# ProProject_caotai_ctrl_v2.net
KiCad netlist of a schematic drawn in EasyEDA Pro
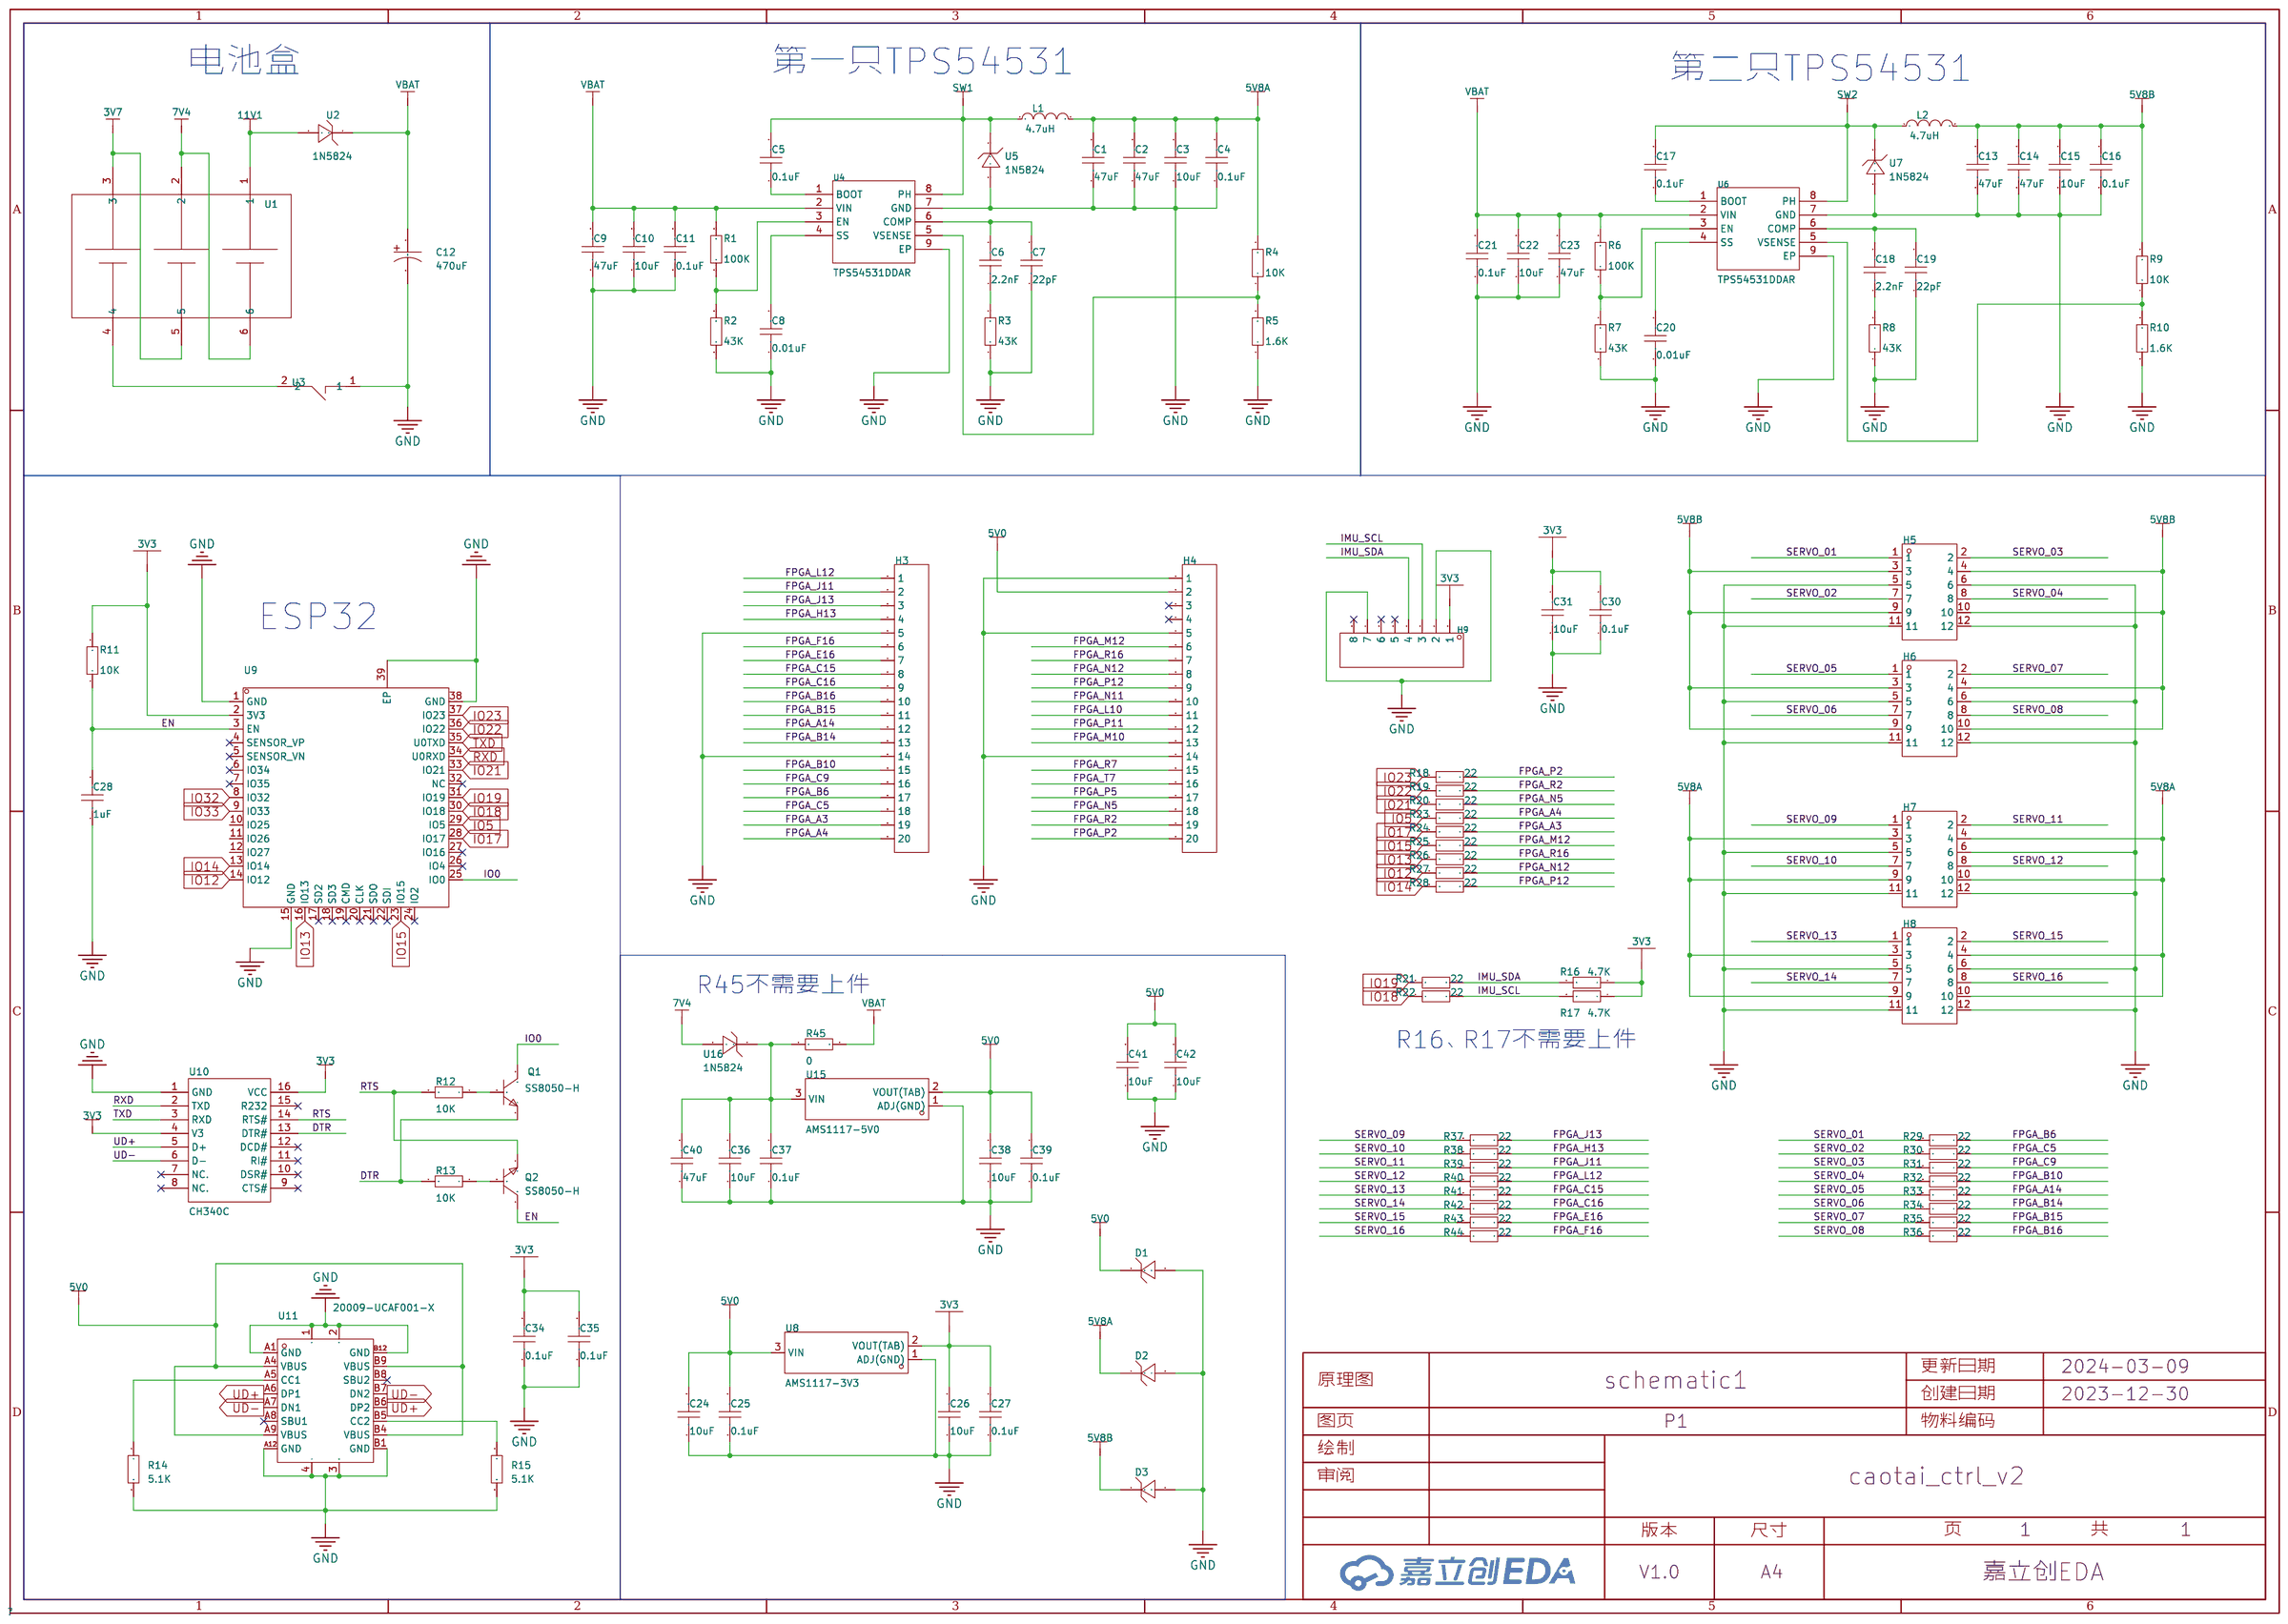
[diagram p0: schematic sheet]

(export (version "E")
  (design (tool "Eeschema 10.0.6"))
  (components
    (comp (ref "C1")
      (value "47uF")
      (footprint "easyedapro:C0603")
      (libsource (lib "easyedapro") (part "CapAcitance"))
    )
    (comp (ref "C2")
      (value "47uF")
      (footprint "easyedapro:C0603")
      (libsource (lib "easyedapro") (part "CapAcitance"))
    )
    (comp (ref "C3")
      (value "10uF")
      (footprint "easyedapro:C0603")
      (libsource (lib "easyedapro") (part "CapAcitance"))
    )
    (comp (ref "C4")
      (value "0.1uF")
      (footprint "easyedapro:C0603")
      (libsource (lib "easyedapro") (part "CapAcitance"))
    )
    (comp (ref "C5")
      (value "0.1uF")
      (footprint "easyedapro:C0603")
      (libsource (lib "easyedapro") (part "CapAcitance"))
    )
    (comp (ref "C6")
      (value "2.2nF")
      (footprint "easyedapro:C0603")
      (libsource (lib "easyedapro") (part "CapAcitance"))
    )
    (comp (ref "C7")
      (value "22pF")
      (footprint "easyedapro:C0603")
      (libsource (lib "easyedapro") (part "CapAcitance"))
    )
    (comp (ref "C8")
      (value "0.01uF")
      (footprint "easyedapro:C0603")
      (libsource (lib "easyedapro") (part "CapAcitance"))
    )
    (comp (ref "C9")
      (value "47uF")
      (footprint "easyedapro:C0603")
      (libsource (lib "easyedapro") (part "CapAcitance"))
    )
    (comp (ref "C10")
      (value "10uF")
      (footprint "easyedapro:C0603")
      (libsource (lib "easyedapro") (part "CapAcitance"))
    )
    (comp (ref "C11")
      (value "0.1uF")
      (footprint "easyedapro:C0603")
      (libsource (lib "easyedapro") (part "CapAcitance"))
    )
    (comp (ref "C12")
      (value "470uF")
      (footprint "easyedapro:CAP-TH_BD10.0-P5.00-D1.0-FD")
      (description "容值:470uF;精度:±20%;额定电压:25V;")
      (fields
        (field (name "Manufacturer Part") "NXB25VB470M10*16_5.0TP")
        (field (name "Manufacturer") "SAMYOUNG(韩国三莹)")
      )
      (libsource (lib "easyedapro") (part "NXB25VB470M10*16_5.0TP"))
    )
    (comp (ref "C13")
      (value "47uF")
      (footprint "easyedapro:C0603")
      (libsource (lib "easyedapro") (part "CapAcitance"))
    )
    (comp (ref "C14")
      (value "47uF")
      (footprint "easyedapro:C0603")
      (libsource (lib "easyedapro") (part "CapAcitance"))
    )
    (comp (ref "C15")
      (value "10uF")
      (footprint "easyedapro:C0603")
      (libsource (lib "easyedapro") (part "CapAcitance"))
    )
    (comp (ref "C16")
      (value "0.1uF")
      (footprint "easyedapro:C0603")
      (libsource (lib "easyedapro") (part "CapAcitance"))
    )
    (comp (ref "C17")
      (value "0.1uF")
      (footprint "easyedapro:C0603")
      (libsource (lib "easyedapro") (part "CapAcitance"))
    )
    (comp (ref "C18")
      (value "2.2nF")
      (footprint "easyedapro:C0603")
      (libsource (lib "easyedapro") (part "CapAcitance"))
    )
    (comp (ref "C19")
      (value "22pF")
      (footprint "easyedapro:C0603")
      (libsource (lib "easyedapro") (part "CapAcitance"))
    )
    (comp (ref "C20")
      (value "0.01uF")
      (footprint "easyedapro:C0603")
      (libsource (lib "easyedapro") (part "CapAcitance"))
    )
    (comp (ref "C21")
      (value "0.1uF")
      (footprint "easyedapro:C0603")
      (libsource (lib "easyedapro") (part "CapAcitance"))
    )
    (comp (ref "C22")
      (value "10uF")
      (footprint "easyedapro:C0603")
      (libsource (lib "easyedapro") (part "CapAcitance"))
    )
    (comp (ref "C23")
      (value "47uF")
      (footprint "easyedapro:C0603")
      (libsource (lib "easyedapro") (part "CapAcitance"))
    )
    (comp (ref "C24")
      (value "10uF")
      (footprint "easyedapro:C0603")
      (libsource (lib "easyedapro") (part "CapAcitance"))
    )
    (comp (ref "C25")
      (value "0.1uF")
      (footprint "easyedapro:C0603")
      (libsource (lib "easyedapro") (part "CapAcitance"))
    )
    (comp (ref "C26")
      (value "10uF")
      (footprint "easyedapro:C0603")
      (libsource (lib "easyedapro") (part "CapAcitance"))
    )
    (comp (ref "C27")
      (value "0.1uF")
      (footprint "easyedapro:C0603")
      (libsource (lib "easyedapro") (part "CapAcitance"))
    )
    (comp (ref "C28")
      (value "1uF")
      (footprint "easyedapro:C0603")
      (libsource (lib "easyedapro") (part "CapAcitance"))
    )
    (comp (ref "C30")
      (value "0.1uF")
      (footprint "easyedapro:C0603")
      (libsource (lib "easyedapro") (part "CapAcitance"))
    )
    (comp (ref "C31")
      (value "10uF")
      (footprint "easyedapro:C0603")
      (libsource (lib "easyedapro") (part "CapAcitance"))
    )
    (comp (ref "C34")
      (value "0.1uF")
      (footprint "easyedapro:C0603")
      (libsource (lib "easyedapro") (part "CapAcitance"))
    )
    (comp (ref "C35")
      (value "0.1uF")
      (footprint "easyedapro:C0603")
      (libsource (lib "easyedapro") (part "CapAcitance"))
    )
    (comp (ref "C36")
      (value "10uF")
      (footprint "easyedapro:C0603")
      (libsource (lib "easyedapro") (part "CapAcitance"))
    )
    (comp (ref "C37")
      (value "0.1uF")
      (footprint "easyedapro:C0603")
      (libsource (lib "easyedapro") (part "CapAcitance"))
    )
    (comp (ref "C38")
      (value "10uF")
      (footprint "easyedapro:C0603")
      (libsource (lib "easyedapro") (part "CapAcitance"))
    )
    (comp (ref "C39")
      (value "0.1uF")
      (footprint "easyedapro:C0603")
      (libsource (lib "easyedapro") (part "CapAcitance"))
    )
    (comp (ref "C40")
      (value "47uF")
      (footprint "easyedapro:C0603")
      (libsource (lib "easyedapro") (part "CapAcitance"))
    )
    (comp (ref "C41")
      (value "10uF")
      (footprint "easyedapro:C0603")
      (libsource (lib "easyedapro") (part "CapAcitance"))
    )
    (comp (ref "C42")
      (value "10uF")
      (footprint "easyedapro:C0603")
      (libsource (lib "easyedapro") (part "CapAcitance"))
    )
    (comp (ref "D1")
      (value "SMBJ24CD-M3/I")
      (footprint "easyedapro:SMB_L4.6-W3.6-LS5.3-RD")
      (fields (field (name "Manufacturer") "VISHAY(威世)"))
      (libsource (lib "easyedapro") (part "SMBJ24CD-M3/I"))
    )
    (comp (ref "D2")
      (value "SMBJ24CD-M3/I")
      (footprint "easyedapro:SMB_L4.6-W3.6-LS5.3-RD")
      (fields (field (name "Manufacturer") "VISHAY(威世)"))
      (libsource (lib "easyedapro") (part "SMBJ24CD-M3/I"))
    )
    (comp (ref "D3")
      (value "SMBJ24CD-M3/I")
      (footprint "easyedapro:SMB_L4.6-W3.6-LS5.3-RD")
      (fields (field (name "Manufacturer") "VISHAY(威世)"))
      (libsource (lib "easyedapro") (part "SMBJ24CD-M3/I"))
    )
    (comp (ref "H3")
      (value "~")
      (footprint "easyedapro:HDR-TH_20P-P2.54-V-F")
      (libsource (lib "easyedapro") (part "HDR-F_2.54_1x20P"))
    )
    (comp (ref "H4")
      (value "~")
      (footprint "easyedapro:HDR-TH_20P-P2.54-V-F")
      (libsource (lib "easyedapro") (part "HDR-F_2.54_1x20P"))
    )
    (comp (ref "H5")
      (value "~")
      (footprint "easyedapro:HDR-TH_12P-P2.54-V-M-R2-C6-S2.54")
      (libsource (lib "easyedapro") (part "HDR-M-2.54_2x6"))
    )
    (comp (ref "H6")
      (value "~")
      (footprint "easyedapro:HDR-TH_12P-P2.54-V-M-R2-C6-S2.54")
      (libsource (lib "easyedapro") (part "HDR-M-2.54_2x6"))
    )
    (comp (ref "H7")
      (value "~")
      (footprint "easyedapro:HDR-TH_12P-P2.54-V-M-R2-C6-S2.54")
      (libsource (lib "easyedapro") (part "HDR-M-2.54_2x6"))
    )
    (comp (ref "H8")
      (value "~")
      (footprint "easyedapro:HDR-TH_12P-P2.54-V-M-R2-C6-S2.54")
      (libsource (lib "easyedapro") (part "HDR-M-2.54_2x6"))
    )
    (comp (ref "H9")
      (value "~")
      (footprint "easyedapro:HDR-TH_8P-P2.54-V-M")
      (libsource (lib "easyedapro") (part "Header-Male-2.54_1x8"))
    )
    (comp (ref "L1")
      (value "4.7uH")
      (footprint "easyedapro:IND-SMD_L10.2-W10.0_MS104R")
      (libsource (lib "easyedapro") (part "CDRH104_2_C9900021916"))
    )
    (comp (ref "L2")
      (value "4.7uH")
      (footprint "easyedapro:IND-SMD_L10.2-W10.0_MS104R")
      (libsource (lib "easyedapro") (part "CDRH104_2_C9900021916"))
    )
    (comp (ref "Q1")
      (value "SS8050-H")
      (footprint "easyedapro:SOT-23-3_L2.9-W1.3-P1.90-LS2.4-BR")
      (fields (field (name "Manufacturer") "YANGJIE(扬杰)"))
      (libsource (lib "easyedapro") (part "SS8050-H"))
    )
    (comp (ref "Q2")
      (value "SS8050-H")
      (footprint "easyedapro:SOT-23-3_L2.9-W1.3-P1.90-LS2.4-BR")
      (fields (field (name "Manufacturer") "YANGJIE(扬杰)"))
      (libsource (lib "easyedapro") (part "SS8050-H"))
    )
    (comp (ref "R1") (value "100K") (footprint "easyedapro:R0603") (libsource (lib "easyedapro") (part "电阻")))
    (comp (ref "R2") (value "43K") (footprint "easyedapro:R0603") (libsource (lib "easyedapro") (part "电阻")))
    (comp (ref "R3") (value "43K") (footprint "easyedapro:R0603") (libsource (lib "easyedapro") (part "电阻")))
    (comp (ref "R4") (value "10K") (footprint "easyedapro:R0603") (libsource (lib "easyedapro") (part "电阻")))
    (comp (ref "R5") (value "1.6K") (footprint "easyedapro:R0603") (libsource (lib "easyedapro") (part "电阻")))
    (comp (ref "R6") (value "100K") (footprint "easyedapro:R0603") (libsource (lib "easyedapro") (part "电阻")))
    (comp (ref "R7") (value "43K") (footprint "easyedapro:R0603") (libsource (lib "easyedapro") (part "电阻")))
    (comp (ref "R8") (value "43K") (footprint "easyedapro:R0603") (libsource (lib "easyedapro") (part "电阻")))
    (comp (ref "R9") (value "10K") (footprint "easyedapro:R0603") (libsource (lib "easyedapro") (part "电阻")))
    (comp (ref "R10")
      (value "1.6K")
      (footprint "easyedapro:R0603")
      (libsource (lib "easyedapro") (part "电阻"))
    )
    (comp (ref "R11") (value "10K") (footprint "easyedapro:R0603") (libsource (lib "easyedapro") (part "电阻")))
    (comp (ref "R12") (value "10K") (footprint "easyedapro:R0603") (libsource (lib "easyedapro") (part "电阻")))
    (comp (ref "R13") (value "10K") (footprint "easyedapro:R0603") (libsource (lib "easyedapro") (part "电阻")))
    (comp (ref "R14")
      (value "5.1K")
      (footprint "easyedapro:R0603")
      (libsource (lib "easyedapro") (part "电阻"))
    )
    (comp (ref "R15")
      (value "5.1K")
      (footprint "easyedapro:R0603")
      (libsource (lib "easyedapro") (part "电阻"))
    )
    (comp (ref "R16")
      (value "4.7K")
      (footprint "easyedapro:R0603")
      (libsource (lib "easyedapro") (part "电阻"))
    )
    (comp (ref "R17")
      (value "4.7K")
      (footprint "easyedapro:R0603")
      (libsource (lib "easyedapro") (part "电阻"))
    )
    (comp (ref "R18") (value "22") (footprint "easyedapro:R0603") (libsource (lib "easyedapro") (part "电阻")))
    (comp (ref "R19") (value "22") (footprint "easyedapro:R0603") (libsource (lib "easyedapro") (part "电阻")))
    (comp (ref "R20") (value "22") (footprint "easyedapro:R0603") (libsource (lib "easyedapro") (part "电阻")))
    (comp (ref "R21") (value "22") (footprint "easyedapro:R0603") (libsource (lib "easyedapro") (part "电阻")))
    (comp (ref "R22") (value "22") (footprint "easyedapro:R0603") (libsource (lib "easyedapro") (part "电阻")))
    (comp (ref "R23") (value "22") (footprint "easyedapro:R0603") (libsource (lib "easyedapro") (part "电阻")))
    (comp (ref "R24") (value "22") (footprint "easyedapro:R0603") (libsource (lib "easyedapro") (part "电阻")))
    (comp (ref "R25") (value "22") (footprint "easyedapro:R0603") (libsource (lib "easyedapro") (part "电阻")))
    (comp (ref "R26") (value "22") (footprint "easyedapro:R0603") (libsource (lib "easyedapro") (part "电阻")))
    (comp (ref "R27") (value "22") (footprint "easyedapro:R0603") (libsource (lib "easyedapro") (part "电阻")))
    (comp (ref "R28") (value "22") (footprint "easyedapro:R0603") (libsource (lib "easyedapro") (part "电阻")))
    (comp (ref "R29") (value "22") (footprint "easyedapro:R0603") (libsource (lib "easyedapro") (part "电阻")))
    (comp (ref "R30") (value "22") (footprint "easyedapro:R0603") (libsource (lib "easyedapro") (part "电阻")))
    (comp (ref "R31") (value "22") (footprint "easyedapro:R0603") (libsource (lib "easyedapro") (part "电阻")))
    (comp (ref "R32") (value "22") (footprint "easyedapro:R0603") (libsource (lib "easyedapro") (part "电阻")))
    (comp (ref "R33") (value "22") (footprint "easyedapro:R0603") (libsource (lib "easyedapro") (part "电阻")))
    (comp (ref "R34") (value "22") (footprint "easyedapro:R0603") (libsource (lib "easyedapro") (part "电阻")))
    (comp (ref "R35") (value "22") (footprint "easyedapro:R0603") (libsource (lib "easyedapro") (part "电阻")))
    (comp (ref "R36") (value "22") (footprint "easyedapro:R0603") (libsource (lib "easyedapro") (part "电阻")))
    (comp (ref "R37") (value "22") (footprint "easyedapro:R0603") (libsource (lib "easyedapro") (part "电阻")))
    (comp (ref "R38") (value "22") (footprint "easyedapro:R0603") (libsource (lib "easyedapro") (part "电阻")))
    (comp (ref "R39") (value "22") (footprint "easyedapro:R0603") (libsource (lib "easyedapro") (part "电阻")))
    (comp (ref "R40") (value "22") (footprint "easyedapro:R0603") (libsource (lib "easyedapro") (part "电阻")))
    (comp (ref "R41") (value "22") (footprint "easyedapro:R0603") (libsource (lib "easyedapro") (part "电阻")))
    (comp (ref "R42") (value "22") (footprint "easyedapro:R0603") (libsource (lib "easyedapro") (part "电阻")))
    (comp (ref "R43") (value "22") (footprint "easyedapro:R0603") (libsource (lib "easyedapro") (part "电阻")))
    (comp (ref "R44") (value "22") (footprint "easyedapro:R0603") (libsource (lib "easyedapro") (part "电阻")))
    (comp (ref "R45") (value "0") (footprint "easyedapro:R0603") (libsource (lib "easyedapro") (part "电阻")))
    (comp (ref "U1")
      (value "~")
      (footprint "easyedapro:3节18650插针")
      (libsource (lib "easyedapro") (part "3节18650电池盒插针"))
    )
    (comp (ref "U2")
      (value "1N5824")
      (footprint "easyedapro:SMB_L4.4-W3.6-LS5.2-RD")
      (libsource (lib "easyedapro") (part "1N5824-SMB"))
    )
    (comp (ref "U3")
      (value "KCD11船型开关")
      (footprint "easyedapro:SW-TH_KCD11")
      (libsource (lib "easyedapro") (part "KCD11船型开关"))
    )
    (comp (ref "U4")
      (value "TPS54531DDAR")
      (footprint "easyedapro:SOIC-8_L5.0-W4.0-P1.27-LS6.0-BL-EP2.0")
      (description "功能类型:降压型;输出类型:可调;输入电压:3.5V~28V;输出电压:800mV~26.04V;输出电流(最大值):5A;")
      (fields (field (name "Manufacturer") "TI(德州仪器)"))
      (libsource (lib "easyedapro") (part "TPS54531DDAR"))
    )
    (comp (ref "U5")
      (value "1N5824")
      (footprint "easyedapro:SMB_L4.4-W3.6-LS5.2-RD")
      (libsource (lib "easyedapro") (part "1N5824-SMB"))
    )
    (comp (ref "U6")
      (value "TPS54531DDAR")
      (footprint "easyedapro:SOIC-8_L5.0-W4.0-P1.27-LS6.0-BL-EP2.0")
      (description "功能类型:降压型;输出类型:可调;输入电压:3.5V~28V;输出电压:800mV~26.04V;输出电流(最大值):5A;")
      (fields (field (name "Manufacturer") "TI(德州仪器)"))
      (libsource (lib "easyedapro") (part "TPS54531DDAR"))
    )
    (comp (ref "U7")
      (value "1N5824")
      (footprint "easyedapro:SMB_L4.4-W3.6-LS5.2-RD")
      (libsource (lib "easyedapro") (part "1N5824-SMB"))
    )
    (comp (ref "U8")
      (value "AMS1117-3V3")
      (footprint "easyedapro:SOT-89-3_L4.5-W2.5-P1.50-LS4.1-BL")
      (fields (field (name "Manufacturer") "UMW(广东友台半导体)"))
      (libsource (lib "easyedapro") (part "AMS1117-ADJS"))
    )
    (comp (ref "U9")
      (value "~")
      (footprint "easyedapro:wirelm-smd_esp32-s")
      (fields (field (name "Manufacturer Part") "ESP32-S") (field (name "Manufacturer") "Ai-Thinker(安信可)"))
      (libsource (lib "easyedapro") (part "esp32-s"))
    )
    (comp (ref "U10")
      (value "CH340C")
      (footprint "easyedapro:SOP-16_L10.0-W3.9-P1.27-LS6.0-BL")
      (description "类型:Transceiver;协议类别:USB 2.0;驱动器/接收器数:-;数据速率:2Mbps;")
      (fields (field (name "Manufacturer") "WCH(南京沁恒)"))
      (libsource (lib "easyedapro") (part "CH340C"))
    )
    (comp (ref "U11")
      (value "20009-UCAF001-X")
      (footprint "easyedapro:TYPE-C-SMD_20009-UCAF001-X")
      (fields (field (name "Manufacturer") "MINTRON(明硕)"))
      (libsource (lib "easyedapro") (part "20009-UCAF001-X"))
    )
    (comp (ref "U15")
      (value "AMS1117-5V0")
      (footprint "easyedapro:SOT-89-3_L4.5-W2.5-P1.50-LS4.1-BL")
      (fields (field (name "Manufacturer") "UMW(广东友台半导体)"))
      (libsource (lib "easyedapro") (part "AMS1117-ADJS"))
    )
    (comp (ref "U16")
      (value "1N5824")
      (footprint "easyedapro:SMB_L4.4-W3.6-LS5.2-RD")
      (libsource (lib "easyedapro") (part "1N5824-SMB"))
    )
  )
  (nets
    (net (code "1") (name "/DTR") (class "Default")
      (node (ref "Q1") (pin "2") (pinfunction "E_2") (pintype "input"))
      (node (ref "R13") (pin "2") (pinfunction "2_2") (pintype "input"))
      (node (ref "U10") (pin "13") (pinfunction "DTR#_13") (pintype "input"))
    )
    (net (code "2") (name "/EN") (class "Default")
      (node (ref "C28") (pin "2") (pinfunction "2_2") (pintype "input"))
      (node (ref "Q2") (pin "3") (pinfunction "C_3") (pintype "input"))
      (node (ref "R11") (pin "1") (pinfunction "1_1") (pintype "input"))
      (node (ref "U9") (pin "3") (pinfunction "EN_3") (pintype "input"))
    )
    (net (code "3") (name "/FPGA_A3") (class "Default")
      (node (ref "H3") (pin "19") (pinfunction "19_19") (pintype "input"))
      (node (ref "R24") (pin "1") (pinfunction "1_1") (pintype "input"))
    )
    (net (code "4") (name "/FPGA_A4") (class "Default")
      (node (ref "H3") (pin "20") (pinfunction "20_20") (pintype "input"))
      (node (ref "R23") (pin "1") (pinfunction "1_1") (pintype "input"))
    )
    (net (code "5") (name "/FPGA_A14") (class "Default")
      (node (ref "H3") (pin "12") (pinfunction "12_12") (pintype "input"))
      (node (ref "R33") (pin "1") (pinfunction "1_1") (pintype "input"))
    )
    (net (code "6") (name "/FPGA_B6") (class "Default")
      (node (ref "H3") (pin "17") (pinfunction "17_17") (pintype "input"))
      (node (ref "R29") (pin "1") (pinfunction "1_1") (pintype "input"))
    )
    (net (code "7") (name "/FPGA_B10") (class "Default")
      (node (ref "H3") (pin "15") (pinfunction "15_15") (pintype "input"))
      (node (ref "R32") (pin "1") (pinfunction "1_1") (pintype "input"))
    )
    (net (code "8") (name "/FPGA_B14") (class "Default")
      (node (ref "H3") (pin "13") (pinfunction "13_13") (pintype "input"))
      (node (ref "R34") (pin "1") (pinfunction "1_1") (pintype "input"))
    )
    (net (code "9") (name "/FPGA_B15") (class "Default")
      (node (ref "H3") (pin "11") (pinfunction "11_11") (pintype "input"))
      (node (ref "R35") (pin "1") (pinfunction "1_1") (pintype "input"))
    )
    (net (code "10") (name "/FPGA_B16") (class "Default")
      (node (ref "H3") (pin "10") (pinfunction "10_10") (pintype "input"))
      (node (ref "R36") (pin "1") (pinfunction "1_1") (pintype "input"))
    )
    (net (code "11") (name "/FPGA_C5") (class "Default")
      (node (ref "H3") (pin "18") (pinfunction "18_18") (pintype "input"))
      (node (ref "R30") (pin "1") (pinfunction "1_1") (pintype "input"))
    )
    (net (code "12") (name "/FPGA_C9") (class "Default")
      (node (ref "H3") (pin "16") (pinfunction "16_16") (pintype "input"))
      (node (ref "R31") (pin "1") (pinfunction "1_1") (pintype "input"))
    )
    (net (code "13") (name "/FPGA_C15") (class "Default")
      (node (ref "H3") (pin "8") (pinfunction "8_8") (pintype "input"))
      (node (ref "R41") (pin "1") (pinfunction "1_1") (pintype "input"))
    )
    (net (code "14") (name "/FPGA_C16") (class "Default")
      (node (ref "H3") (pin "9") (pinfunction "9_9") (pintype "input"))
      (node (ref "R42") (pin "1") (pinfunction "1_1") (pintype "input"))
    )
    (net (code "15") (name "/FPGA_E16") (class "Default")
      (node (ref "H3") (pin "7") (pinfunction "7_7") (pintype "input"))
      (node (ref "R43") (pin "1") (pinfunction "1_1") (pintype "input"))
    )
    (net (code "16") (name "/FPGA_F16") (class "Default")
      (node (ref "H3") (pin "6") (pinfunction "6_6") (pintype "input"))
      (node (ref "R44") (pin "1") (pinfunction "1_1") (pintype "input"))
    )
    (net (code "17") (name "/FPGA_H13") (class "Default")
      (node (ref "H3") (pin "4") (pinfunction "4_4") (pintype "input"))
      (node (ref "R38") (pin "1") (pinfunction "1_1") (pintype "input"))
    )
    (net (code "18") (name "/FPGA_J11") (class "Default")
      (node (ref "H3") (pin "2") (pinfunction "2_2") (pintype "input"))
      (node (ref "R39") (pin "1") (pinfunction "1_1") (pintype "input"))
    )
    (net (code "19") (name "/FPGA_J13") (class "Default")
      (node (ref "H3") (pin "3") (pinfunction "3_3") (pintype "input"))
      (node (ref "R37") (pin "1") (pinfunction "1_1") (pintype "input"))
    )
    (net (code "20") (name "/FPGA_L10") (class "Default")
      (node (ref "H4") (pin "11") (pinfunction "11_11") (pintype "input"))
    )
    (net (code "21") (name "/FPGA_L12") (class "Default")
      (node (ref "H3") (pin "1") (pinfunction "1_1") (pintype "input"))
      (node (ref "R40") (pin "1") (pinfunction "1_1") (pintype "input"))
    )
    (net (code "22") (name "/FPGA_M10") (class "Default")
      (node (ref "H4") (pin "13") (pinfunction "13_13") (pintype "input"))
    )
    (net (code "23") (name "/FPGA_M12") (class "Default")
      (node (ref "H4") (pin "6") (pinfunction "6_6") (pintype "input"))
      (node (ref "R25") (pin "1") (pinfunction "1_1") (pintype "input"))
    )
    (net (code "24") (name "/FPGA_N5") (class "Default")
      (node (ref "H4") (pin "18") (pinfunction "18_18") (pintype "input"))
      (node (ref "R20") (pin "1") (pinfunction "1_1") (pintype "input"))
    )
    (net (code "25") (name "/FPGA_N11") (class "Default")
      (node (ref "H4") (pin "10") (pinfunction "10_10") (pintype "input"))
    )
    (net (code "26") (name "/FPGA_N12") (class "Default")
      (node (ref "H4") (pin "8") (pinfunction "8_8") (pintype "input"))
      (node (ref "R27") (pin "1") (pinfunction "1_1") (pintype "input"))
    )
    (net (code "27") (name "/FPGA_P2") (class "Default")
      (node (ref "H4") (pin "20") (pinfunction "20_20") (pintype "input"))
      (node (ref "R18") (pin "1") (pinfunction "1_1") (pintype "input"))
    )
    (net (code "28") (name "/FPGA_P5") (class "Default")
      (node (ref "H4") (pin "17") (pinfunction "17_17") (pintype "input"))
    )
    (net (code "29") (name "/FPGA_P11") (class "Default")
      (node (ref "H4") (pin "12") (pinfunction "12_12") (pintype "input"))
    )
    (net (code "30") (name "/FPGA_P12") (class "Default")
      (node (ref "H4") (pin "9") (pinfunction "9_9") (pintype "input"))
      (node (ref "R28") (pin "1") (pinfunction "1_1") (pintype "input"))
    )
    (net (code "31") (name "/FPGA_R2") (class "Default")
      (node (ref "H4") (pin "19") (pinfunction "19_19") (pintype "input"))
      (node (ref "R19") (pin "1") (pinfunction "1_1") (pintype "input"))
    )
    (net (code "32") (name "/FPGA_R7") (class "Default")
      (node (ref "H4") (pin "15") (pinfunction "15_15") (pintype "input"))
    )
    (net (code "33") (name "/FPGA_R16") (class "Default")
      (node (ref "H4") (pin "7") (pinfunction "7_7") (pintype "input"))
      (node (ref "R26") (pin "1") (pinfunction "1_1") (pintype "input"))
    )
    (net (code "34") (name "/FPGA_T7") (class "Default")
      (node (ref "H4") (pin "16") (pinfunction "16_16") (pintype "input"))
    )
    (net (code "35") (name "/IMU_SCL") (class "Default")
      (node (ref "H9") (pin "3") (pinfunction "3_3") (pintype "input"))
      (node (ref "R17") (pin "2") (pinfunction "2_2") (pintype "input"))
      (node (ref "R22") (pin "1") (pinfunction "1_1") (pintype "input"))
    )
    (net (code "36") (name "/IMU_SDA") (class "Default")
      (node (ref "H9") (pin "4") (pinfunction "4_4") (pintype "input"))
      (node (ref "R16") (pin "2") (pinfunction "2_2") (pintype "input"))
      (node (ref "R21") (pin "1") (pinfunction "1_1") (pintype "input"))
    )
    (net (code "37") (name "/IO0") (class "Default")
      (node (ref "Q1") (pin "3") (pinfunction "C_3") (pintype "input"))
      (node (ref "U9") (pin "25") (pinfunction "IO0_25") (pintype "input"))
    )
    (net (code "38") (name "/RTS") (class "Default")
      (node (ref "Q2") (pin "2") (pinfunction "E_2") (pintype "input"))
      (node (ref "R12") (pin "2") (pinfunction "2_2") (pintype "input"))
      (node (ref "U10") (pin "14") (pinfunction "RTS#_14") (pintype "input"))
    )
    (net (code "39") (name "/SERVO_01") (class "Default")
      (node (ref "H5") (pin "1") (pinfunction "1_1") (pintype "input"))
      (node (ref "R29") (pin "2") (pinfunction "2_2") (pintype "input"))
    )
    (net (code "40") (name "/SERVO_02") (class "Default")
      (node (ref "H5") (pin "7") (pinfunction "7_7") (pintype "input"))
      (node (ref "R30") (pin "2") (pinfunction "2_2") (pintype "input"))
    )
    (net (code "41") (name "/SERVO_03") (class "Default")
      (node (ref "H5") (pin "2") (pinfunction "2_2") (pintype "input"))
      (node (ref "R31") (pin "2") (pinfunction "2_2") (pintype "input"))
    )
    (net (code "42") (name "/SERVO_04") (class "Default")
      (node (ref "H5") (pin "8") (pinfunction "8_8") (pintype "input"))
      (node (ref "R32") (pin "2") (pinfunction "2_2") (pintype "input"))
    )
    (net (code "43") (name "/SERVO_05") (class "Default")
      (node (ref "H6") (pin "1") (pinfunction "1_1") (pintype "input"))
      (node (ref "R33") (pin "2") (pinfunction "2_2") (pintype "input"))
    )
    (net (code "44") (name "/SERVO_06") (class "Default")
      (node (ref "H6") (pin "7") (pinfunction "7_7") (pintype "input"))
      (node (ref "R34") (pin "2") (pinfunction "2_2") (pintype "input"))
    )
    (net (code "45") (name "/SERVO_07") (class "Default")
      (node (ref "H6") (pin "2") (pinfunction "2_2") (pintype "input"))
      (node (ref "R35") (pin "2") (pinfunction "2_2") (pintype "input"))
    )
    (net (code "46") (name "/SERVO_08") (class "Default")
      (node (ref "H6") (pin "8") (pinfunction "8_8") (pintype "input"))
      (node (ref "R36") (pin "2") (pinfunction "2_2") (pintype "input"))
    )
    (net (code "47") (name "/SERVO_09") (class "Default")
      (node (ref "H7") (pin "1") (pinfunction "1_1") (pintype "input"))
      (node (ref "R37") (pin "2") (pinfunction "2_2") (pintype "input"))
    )
    (net (code "48") (name "/SERVO_10") (class "Default")
      (node (ref "H7") (pin "7") (pinfunction "7_7") (pintype "input"))
      (node (ref "R38") (pin "2") (pinfunction "2_2") (pintype "input"))
    )
    (net (code "49") (name "/SERVO_11") (class "Default")
      (node (ref "H7") (pin "2") (pinfunction "2_2") (pintype "input"))
      (node (ref "R39") (pin "2") (pinfunction "2_2") (pintype "input"))
    )
    (net (code "50") (name "/SERVO_12") (class "Default")
      (node (ref "H7") (pin "8") (pinfunction "8_8") (pintype "input"))
      (node (ref "R40") (pin "2") (pinfunction "2_2") (pintype "input"))
    )
    (net (code "51") (name "/SERVO_13") (class "Default")
      (node (ref "H8") (pin "1") (pinfunction "1_1") (pintype "input"))
      (node (ref "R41") (pin "2") (pinfunction "2_2") (pintype "input"))
    )
    (net (code "52") (name "/SERVO_14") (class "Default")
      (node (ref "H8") (pin "7") (pinfunction "7_7") (pintype "input"))
      (node (ref "R42") (pin "2") (pinfunction "2_2") (pintype "input"))
    )
    (net (code "53") (name "/SERVO_15") (class "Default")
      (node (ref "H8") (pin "2") (pinfunction "2_2") (pintype "input"))
      (node (ref "R43") (pin "2") (pinfunction "2_2") (pintype "input"))
    )
    (net (code "54") (name "/SERVO_16") (class "Default")
      (node (ref "H8") (pin "8") (pinfunction "8_8") (pintype "input"))
      (node (ref "R44") (pin "2") (pinfunction "2_2") (pintype "input"))
    )
    (net (code "55") (name "3V3") (class "Default")
      (node (ref "C26") (pin "2") (pinfunction "2_2") (pintype "input"))
      (node (ref "C27") (pin "2") (pinfunction "2_2") (pintype "input"))
      (node (ref "C30") (pin "2") (pinfunction "2_2") (pintype "input"))
      (node (ref "C31") (pin "1") (pinfunction "1_1") (pintype "input"))
      (node (ref "C34") (pin "2") (pinfunction "2_2") (pintype "input"))
      (node (ref "C35") (pin "2") (pinfunction "2_2") (pintype "input"))
      (node (ref "H9") (pin "1") (pinfunction "1_1") (pintype "input"))
      (node (ref "R11") (pin "2") (pinfunction "2_2") (pintype "input"))
      (node (ref "R16") (pin "1") (pinfunction "1_1") (pintype "input"))
      (node (ref "R17") (pin "1") (pinfunction "1_1") (pintype "input"))
      (node (ref "U10") (pin "16") (pinfunction "VCC_16") (pintype "input"))
      (node (ref "U10") (pin "4") (pinfunction "V3_4") (pintype "input"))
      (node (ref "U8") (pin "2") (pinfunction "VOUT(TAB)_2") (pintype "input"))
      (node (ref "U9") (pin "2") (pinfunction "3V3_2") (pintype "input"))
    )
    (net (code "56") (name "3V7") (class "Default")
      (node (ref "U1") (pin "3") (pinfunction "3_3") (pintype "input"))
      (node (ref "U1") (pin "5") (pinfunction "5_5") (pintype "input"))
    )
    (net (code "57") (name "5V0") (class "Default")
      (node (ref "C24") (pin "2") (pinfunction "2_2") (pintype "input"))
      (node (ref "C25") (pin "2") (pinfunction "2_2") (pintype "input"))
      (node (ref "C38") (pin "2") (pinfunction "2_2") (pintype "input"))
      (node (ref "C39") (pin "2") (pinfunction "2_2") (pintype "input"))
      (node (ref "C41") (pin "2") (pinfunction "2_2") (pintype "input"))
      (node (ref "C42") (pin "2") (pinfunction "2_2") (pintype "input"))
      (node (ref "D1") (pin "1") (pinfunction "K_1") (pintype "input"))
      (node (ref "H4") (pin "2") (pinfunction "2_2") (pintype "input"))
      (node (ref "U11") (pin "A4") (pinfunction "VBUS_A4") (pintype "input"))
      (node (ref "U11") (pin "A9") (pinfunction "VBUS_A9") (pintype "input"))
      (node (ref "U11") (pin "B4") (pinfunction "VBUS_B4") (pintype "input"))
      (node (ref "U11") (pin "B9") (pinfunction "VBUS_B9") (pintype "input"))
      (node (ref "U15") (pin "2") (pinfunction "VOUT(TAB)_2") (pintype "input"))
      (node (ref "U8") (pin "3") (pinfunction "VIN_3") (pintype "input"))
    )
    (net (code "58") (name "5V8A") (class "Default")
      (node (ref "C1") (pin "2") (pinfunction "2_2") (pintype "input"))
      (node (ref "C2") (pin "2") (pinfunction "2_2") (pintype "input"))
      (node (ref "C3") (pin "2") (pinfunction "2_2") (pintype "input"))
      (node (ref "C4") (pin "2") (pinfunction "2_2") (pintype "input"))
      (node (ref "D2") (pin "1") (pinfunction "K_1") (pintype "input"))
      (node (ref "H7") (pin "10") (pinfunction "10_10") (pintype "input"))
      (node (ref "H7") (pin "3") (pinfunction "3_3") (pintype "input"))
      (node (ref "H7") (pin "4") (pinfunction "4_4") (pintype "input"))
      (node (ref "H7") (pin "9") (pinfunction "9_9") (pintype "input"))
      (node (ref "H8") (pin "10") (pinfunction "10_10") (pintype "input"))
      (node (ref "H8") (pin "3") (pinfunction "3_3") (pintype "input"))
      (node (ref "H8") (pin "4") (pinfunction "4_4") (pintype "input"))
      (node (ref "H8") (pin "9") (pinfunction "9_9") (pintype "input"))
      (node (ref "L1") (pin "2") (pinfunction "2_2") (pintype "input"))
      (node (ref "R4") (pin "2") (pinfunction "2_2") (pintype "input"))
    )
    (net (code "59") (name "5V8B") (class "Default")
      (node (ref "C13") (pin "2") (pinfunction "2_2") (pintype "input"))
      (node (ref "C14") (pin "2") (pinfunction "2_2") (pintype "input"))
      (node (ref "C15") (pin "2") (pinfunction "2_2") (pintype "input"))
      (node (ref "C16") (pin "2") (pinfunction "2_2") (pintype "input"))
      (node (ref "D3") (pin "1") (pinfunction "K_1") (pintype "input"))
      (node (ref "H5") (pin "10") (pinfunction "10_10") (pintype "input"))
      (node (ref "H5") (pin "3") (pinfunction "3_3") (pintype "input"))
      (node (ref "H5") (pin "4") (pinfunction "4_4") (pintype "input"))
      (node (ref "H5") (pin "9") (pinfunction "9_9") (pintype "input"))
      (node (ref "H6") (pin "10") (pinfunction "10_10") (pintype "input"))
      (node (ref "H6") (pin "3") (pinfunction "3_3") (pintype "input"))
      (node (ref "H6") (pin "4") (pinfunction "4_4") (pintype "input"))
      (node (ref "H6") (pin "9") (pinfunction "9_9") (pintype "input"))
      (node (ref "L2") (pin "2") (pinfunction "2_2") (pintype "input"))
      (node (ref "R9") (pin "2") (pinfunction "2_2") (pintype "input"))
    )
    (net (code "60") (name "7V4") (class "Default")
      (node (ref "U1") (pin "2") (pinfunction "2_2") (pintype "input"))
      (node (ref "U1") (pin "6") (pinfunction "6_6") (pintype "input"))
      (node (ref "U16") (pin "2") (pinfunction "A_2") (pintype "input"))
    )
    (net (code "61") (name "11V1") (class "Default")
      (node (ref "U1") (pin "1") (pinfunction "1_1") (pintype "input"))
      (node (ref "U2") (pin "2") (pinfunction "A_2") (pintype "input"))
    )
    (net (code "62") (name "GND") (class "Default")
      (node (ref "C1") (pin "1") (pinfunction "1_1") (pintype "input"))
      (node (ref "C10") (pin "1") (pinfunction "1_1") (pintype "input"))
      (node (ref "C11") (pin "1") (pinfunction "1_1") (pintype "input"))
      (node (ref "C12") (pin "2") (pinfunction "2_2") (pintype "input"))
      (node (ref "C13") (pin "1") (pinfunction "1_1") (pintype "input"))
      (node (ref "C14") (pin "1") (pinfunction "1_1") (pintype "input"))
      (node (ref "C15") (pin "1") (pinfunction "1_1") (pintype "input"))
      (node (ref "C16") (pin "1") (pinfunction "1_1") (pintype "input"))
      (node (ref "C19") (pin "1") (pinfunction "1_1") (pintype "input"))
      (node (ref "C2") (pin "1") (pinfunction "1_1") (pintype "input"))
      (node (ref "C20") (pin "1") (pinfunction "1_1") (pintype "input"))
      (node (ref "C21") (pin "1") (pinfunction "1_1") (pintype "input"))
      (node (ref "C22") (pin "1") (pinfunction "1_1") (pintype "input"))
      (node (ref "C23") (pin "1") (pinfunction "1_1") (pintype "input"))
      (node (ref "C24") (pin "1") (pinfunction "1_1") (pintype "input"))
      (node (ref "C25") (pin "1") (pinfunction "1_1") (pintype "input"))
      (node (ref "C26") (pin "1") (pinfunction "1_1") (pintype "input"))
      (node (ref "C27") (pin "1") (pinfunction "1_1") (pintype "input"))
      (node (ref "C28") (pin "1") (pinfunction "1_1") (pintype "input"))
      (node (ref "C3") (pin "1") (pinfunction "1_1") (pintype "input"))
      (node (ref "C30") (pin "1") (pinfunction "1_1") (pintype "input"))
      (node (ref "C31") (pin "2") (pinfunction "2_2") (pintype "input"))
      (node (ref "C34") (pin "1") (pinfunction "1_1") (pintype "input"))
      (node (ref "C35") (pin "1") (pinfunction "1_1") (pintype "input"))
      (node (ref "C36") (pin "1") (pinfunction "1_1") (pintype "input"))
      (node (ref "C37") (pin "1") (pinfunction "1_1") (pintype "input"))
      (node (ref "C38") (pin "1") (pinfunction "1_1") (pintype "input"))
      (node (ref "C39") (pin "1") (pinfunction "1_1") (pintype "input"))
      (node (ref "C4") (pin "1") (pinfunction "1_1") (pintype "input"))
      (node (ref "C40") (pin "1") (pinfunction "1_1") (pintype "input"))
      (node (ref "C41") (pin "1") (pinfunction "1_1") (pintype "input"))
      (node (ref "C42") (pin "1") (pinfunction "1_1") (pintype "input"))
      (node (ref "C7") (pin "1") (pinfunction "1_1") (pintype "input"))
      (node (ref "C8") (pin "1") (pinfunction "1_1") (pintype "input"))
      (node (ref "C9") (pin "1") (pinfunction "1_1") (pintype "input"))
      (node (ref "D1") (pin "2") (pinfunction "A_2") (pintype "input"))
      (node (ref "D2") (pin "2") (pinfunction "A_2") (pintype "input"))
      (node (ref "D3") (pin "2") (pinfunction "A_2") (pintype "input"))
      (node (ref "H3") (pin "14") (pinfunction "14_14") (pintype "input"))
      (node (ref "H3") (pin "5") (pinfunction "5_5") (pintype "input"))
      (node (ref "H4") (pin "1") (pinfunction "1_1") (pintype "input"))
      (node (ref "H4") (pin "14") (pinfunction "14_14") (pintype "input"))
      (node (ref "H4") (pin "5") (pinfunction "5_5") (pintype "input"))
      (node (ref "H5") (pin "11") (pinfunction "11_11") (pintype "input"))
      (node (ref "H5") (pin "12") (pinfunction "12_12") (pintype "input"))
      (node (ref "H5") (pin "5") (pinfunction "5_5") (pintype "input"))
      (node (ref "H5") (pin "6") (pinfunction "6_6") (pintype "input"))
      (node (ref "H6") (pin "11") (pinfunction "11_11") (pintype "input"))
      (node (ref "H6") (pin "12") (pinfunction "12_12") (pintype "input"))
      (node (ref "H6") (pin "5") (pinfunction "5_5") (pintype "input"))
      (node (ref "H6") (pin "6") (pinfunction "6_6") (pintype "input"))
      (node (ref "H7") (pin "11") (pinfunction "11_11") (pintype "input"))
      (node (ref "H7") (pin "12") (pinfunction "12_12") (pintype "input"))
      (node (ref "H7") (pin "5") (pinfunction "5_5") (pintype "input"))
      (node (ref "H7") (pin "6") (pinfunction "6_6") (pintype "input"))
      (node (ref "H8") (pin "11") (pinfunction "11_11") (pintype "input"))
      (node (ref "H8") (pin "12") (pinfunction "12_12") (pintype "input"))
      (node (ref "H8") (pin "5") (pinfunction "5_5") (pintype "input"))
      (node (ref "H8") (pin "6") (pinfunction "6_6") (pintype "input"))
      (node (ref "H9") (pin "2") (pinfunction "2_2") (pintype "input"))
      (node (ref "H9") (pin "7") (pinfunction "7_7") (pintype "input"))
      (node (ref "R10") (pin "1") (pinfunction "1_1") (pintype "input"))
      (node (ref "R14") (pin "2") (pinfunction "2_2") (pintype "input"))
      (node (ref "R15") (pin "2") (pinfunction "2_2") (pintype "input"))
      (node (ref "R2") (pin "1") (pinfunction "1_1") (pintype "input"))
      (node (ref "R3") (pin "1") (pinfunction "1_1") (pintype "input"))
      (node (ref "R5") (pin "1") (pinfunction "1_1") (pintype "input"))
      (node (ref "R7") (pin "1") (pinfunction "1_1") (pintype "input"))
      (node (ref "R8") (pin "1") (pinfunction "1_1") (pintype "input"))
      (node (ref "U10") (pin "1") (pinfunction "GND_1") (pintype "input"))
      (node (ref "U11") (pin "1") (pinfunction "1_1") (pintype "input"))
      (node (ref "U11") (pin "2") (pinfunction "2_2") (pintype "input"))
      (node (ref "U11") (pin "3") (pinfunction "3_3") (pintype "input"))
      (node (ref "U11") (pin "4") (pinfunction "4_4") (pintype "input"))
      (node (ref "U11") (pin "A1") (pinfunction "GND_A1") (pintype "input"))
      (node (ref "U11") (pin "A12") (pinfunction "GND_A12") (pintype "input"))
      (node (ref "U11") (pin "B1") (pinfunction "GND_B1") (pintype "input"))
      (node (ref "U11") (pin "B12") (pinfunction "GND_B12") (pintype "input"))
      (node (ref "U15") (pin "1") (pinfunction "ADJ(GND)_1") (pintype "input"))
      (node (ref "U3") (pin "1") (pinfunction "1_1") (pintype "input"))
      (node (ref "U4") (pin "7") (pinfunction "GND_7") (pintype "input"))
      (node (ref "U4") (pin "9") (pinfunction "EP_9") (pintype "input"))
      (node (ref "U5") (pin "2") (pinfunction "A_2") (pintype "input"))
      (node (ref "U6") (pin "7") (pinfunction "GND_7") (pintype "input"))
      (node (ref "U6") (pin "9") (pinfunction "EP_9") (pintype "input"))
      (node (ref "U7") (pin "2") (pinfunction "A_2") (pintype "input"))
      (node (ref "U8") (pin "1") (pinfunction "ADJ(GND)_1") (pintype "input"))
      (node (ref "U9") (pin "1") (pinfunction "GND_1") (pintype "input"))
      (node (ref "U9") (pin "15") (pinfunction "GND_15") (pintype "input"))
      (node (ref "U9") (pin "38") (pinfunction "GND_38") (pintype "input"))
      (node (ref "U9") (pin "39") (pinfunction "EP_39") (pintype "input"))
    )
    (net (code "63") (name "IO5") (class "Default")
      (node (ref "R23") (pin "2") (pinfunction "2_2") (pintype "input"))
      (node (ref "U9") (pin "29") (pinfunction "IO5_29") (pintype "input"))
    )
    (net (code "64") (name "IO12") (class "Default")
      (node (ref "R27") (pin "2") (pinfunction "2_2") (pintype "input"))
      (node (ref "U9") (pin "14") (pinfunction "IO12_14") (pintype "input"))
    )
    (net (code "65") (name "IO13") (class "Default")
      (node (ref "R26") (pin "2") (pinfunction "2_2") (pintype "input"))
      (node (ref "U9") (pin "16") (pinfunction "IO13_16") (pintype "input"))
    )
    (net (code "66") (name "IO14") (class "Default")
      (node (ref "R28") (pin "2") (pinfunction "2_2") (pintype "input"))
      (node (ref "U9") (pin "13") (pinfunction "IO14_13") (pintype "input"))
    )
    (net (code "67") (name "IO15") (class "Default")
      (node (ref "R25") (pin "2") (pinfunction "2_2") (pintype "input"))
      (node (ref "U9") (pin "23") (pinfunction "IO15_23") (pintype "input"))
    )
    (net (code "68") (name "IO17") (class "Default")
      (node (ref "R24") (pin "2") (pinfunction "2_2") (pintype "input"))
      (node (ref "U9") (pin "28") (pinfunction "IO17_28") (pintype "input"))
    )
    (net (code "69") (name "IO18") (class "Default")
      (node (ref "R22") (pin "2") (pinfunction "2_2") (pintype "input"))
      (node (ref "U9") (pin "30") (pinfunction "IO18_30") (pintype "input"))
    )
    (net (code "70") (name "IO19") (class "Default")
      (node (ref "R21") (pin "2") (pinfunction "2_2") (pintype "input"))
      (node (ref "U9") (pin "31") (pinfunction "IO19_31") (pintype "input"))
    )
    (net (code "71") (name "IO21") (class "Default")
      (node (ref "R20") (pin "2") (pinfunction "2_2") (pintype "input"))
      (node (ref "U9") (pin "33") (pinfunction "IO21_33") (pintype "input"))
    )
    (net (code "72") (name "IO22") (class "Default")
      (node (ref "R19") (pin "2") (pinfunction "2_2") (pintype "input"))
      (node (ref "U9") (pin "36") (pinfunction "IO22_36") (pintype "input"))
    )
    (net (code "73") (name "IO23") (class "Default")
      (node (ref "R18") (pin "2") (pinfunction "2_2") (pintype "input"))
      (node (ref "U9") (pin "37") (pinfunction "IO23_37") (pintype "input"))
    )
    (net (code "74") (name "IO32") (class "Default")
      (node (ref "U9") (pin "8") (pinfunction "IO32_8") (pintype "input"))
    )
    (net (code "75") (name "IO33") (class "Default")
      (node (ref "U9") (pin "9") (pinfunction "IO33_9") (pintype "input"))
    )
    (net (code "76") (name "Net-(C6-Pad1)") (class "Default")
      (node (ref "C6") (pin "1") (pinfunction "1_1") (pintype "input"))
      (node (ref "R3") (pin "2") (pinfunction "2_2") (pintype "input"))
    )
    (net (code "77") (name "Net-(C18-Pad1)") (class "Default")
      (node (ref "C18") (pin "1") (pinfunction "1_1") (pintype "input"))
      (node (ref "R8") (pin "2") (pinfunction "2_2") (pintype "input"))
    )
    (net (code "78") (name "Net-(Q1-B)") (class "Default")
      (node (ref "Q1") (pin "1") (pinfunction "B_1") (pintype "input"))
      (node (ref "R12") (pin "1") (pinfunction "1_1") (pintype "input"))
    )
    (net (code "79") (name "Net-(Q2-B)") (class "Default")
      (node (ref "Q2") (pin "1") (pinfunction "B_1") (pintype "input"))
      (node (ref "R13") (pin "1") (pinfunction "1_1") (pintype "input"))
    )
    (net (code "80") (name "Net-(U1-Pad4)") (class "Default")
      (node (ref "U1") (pin "4") (pinfunction "4_4") (pintype "input"))
      (node (ref "U3") (pin "2") (pinfunction "2_2") (pintype "input"))
    )
    (net (code "81") (name "Net-(U4-BOOT)") (class "Default")
      (node (ref "C5") (pin "1") (pinfunction "1_1") (pintype "input"))
      (node (ref "U4") (pin "1") (pinfunction "BOOT_1") (pintype "input"))
    )
    (net (code "82") (name "Net-(U4-COMP)") (class "Default")
      (node (ref "C6") (pin "2") (pinfunction "2_2") (pintype "input"))
      (node (ref "C7") (pin "2") (pinfunction "2_2") (pintype "input"))
      (node (ref "U4") (pin "6") (pinfunction "COMP_6") (pintype "input"))
    )
    (net (code "83") (name "Net-(U4-EN)") (class "Default")
      (node (ref "R1") (pin "1") (pinfunction "1_1") (pintype "input"))
      (node (ref "R2") (pin "2") (pinfunction "2_2") (pintype "input"))
      (node (ref "U4") (pin "3") (pinfunction "EN_3") (pintype "input"))
    )
    (net (code "84") (name "Net-(U4-SS)") (class "Default")
      (node (ref "C8") (pin "2") (pinfunction "2_2") (pintype "input"))
      (node (ref "U4") (pin "4") (pinfunction "SS_4") (pintype "input"))
    )
    (net (code "85") (name "Net-(U4-VSENSE)") (class "Default")
      (node (ref "R4") (pin "1") (pinfunction "1_1") (pintype "input"))
      (node (ref "R5") (pin "2") (pinfunction "2_2") (pintype "input"))
      (node (ref "U4") (pin "5") (pinfunction "VSENSE_5") (pintype "input"))
    )
    (net (code "86") (name "Net-(U6-BOOT)") (class "Default")
      (node (ref "C17") (pin "1") (pinfunction "1_1") (pintype "input"))
      (node (ref "U6") (pin "1") (pinfunction "BOOT_1") (pintype "input"))
    )
    (net (code "87") (name "Net-(U6-COMP)") (class "Default")
      (node (ref "C18") (pin "2") (pinfunction "2_2") (pintype "input"))
      (node (ref "C19") (pin "2") (pinfunction "2_2") (pintype "input"))
      (node (ref "U6") (pin "6") (pinfunction "COMP_6") (pintype "input"))
    )
    (net (code "88") (name "Net-(U6-EN)") (class "Default")
      (node (ref "R6") (pin "1") (pinfunction "1_1") (pintype "input"))
      (node (ref "R7") (pin "2") (pinfunction "2_2") (pintype "input"))
      (node (ref "U6") (pin "3") (pinfunction "EN_3") (pintype "input"))
    )
    (net (code "89") (name "Net-(U6-SS)") (class "Default")
      (node (ref "C20") (pin "2") (pinfunction "2_2") (pintype "input"))
      (node (ref "U6") (pin "4") (pinfunction "SS_4") (pintype "input"))
    )
    (net (code "90") (name "Net-(U6-VSENSE)") (class "Default")
      (node (ref "R10") (pin "2") (pinfunction "2_2") (pintype "input"))
      (node (ref "R9") (pin "1") (pinfunction "1_1") (pintype "input"))
      (node (ref "U6") (pin "5") (pinfunction "VSENSE_5") (pintype "input"))
    )
    (net (code "91") (name "Net-(U11-CC1)") (class "Default")
      (node (ref "R14") (pin "1") (pinfunction "1_1") (pintype "input"))
      (node (ref "U11") (pin "A5") (pinfunction "CC1_A5") (pintype "input"))
    )
    (net (code "92") (name "Net-(U11-CC2)") (class "Default")
      (node (ref "R15") (pin "1") (pinfunction "1_1") (pintype "input"))
      (node (ref "U11") (pin "B5") (pinfunction "CC2_B5") (pintype "input"))
    )
    (net (code "93") (name "Net-(U15-VIN)") (class "Default")
      (node (ref "C36") (pin "2") (pinfunction "2_2") (pintype "input"))
      (node (ref "C37") (pin "2") (pinfunction "2_2") (pintype "input"))
      (node (ref "C40") (pin "2") (pinfunction "2_2") (pintype "input"))
      (node (ref "R45") (pin "2") (pinfunction "2_2") (pintype "input"))
      (node (ref "U15") (pin "3") (pinfunction "VIN_3") (pintype "input"))
      (node (ref "U16") (pin "1") (pinfunction "C_1") (pintype "input"))
    )
    (net (code "94") (name "RXD") (class "Default")
      (node (ref "U10") (pin "2") (pinfunction "TXD_2") (pintype "input"))
      (node (ref "U9") (pin "34") (pinfunction "U0RXD_34") (pintype "input"))
    )
    (net (code "95") (name "SW1") (class "Default")
      (node (ref "C5") (pin "2") (pinfunction "2_2") (pintype "input"))
      (node (ref "L1") (pin "1") (pinfunction "1_1") (pintype "input"))
      (node (ref "U4") (pin "8") (pinfunction "PH_8") (pintype "input"))
      (node (ref "U5") (pin "1") (pinfunction "C_1") (pintype "input"))
    )
    (net (code "96") (name "SW2") (class "Default")
      (node (ref "C17") (pin "2") (pinfunction "2_2") (pintype "input"))
      (node (ref "L2") (pin "1") (pinfunction "1_1") (pintype "input"))
      (node (ref "U6") (pin "8") (pinfunction "PH_8") (pintype "input"))
      (node (ref "U7") (pin "1") (pinfunction "C_1") (pintype "input"))
    )
    (net (code "97") (name "TXD") (class "Default")
      (node (ref "U10") (pin "3") (pinfunction "RXD_3") (pintype "input"))
      (node (ref "U9") (pin "35") (pinfunction "U0TXD_35") (pintype "input"))
    )
    (net (code "98") (name "UD+") (class "Default")
      (node (ref "U10") (pin "5") (pinfunction "D+_5") (pintype "input"))
      (node (ref "U11") (pin "A6") (pinfunction "DP1_A6") (pintype "input"))
      (node (ref "U11") (pin "B6") (pinfunction "DP2_B6") (pintype "input"))
    )
    (net (code "99") (name "UD-") (class "Default")
      (node (ref "U10") (pin "6") (pinfunction "D-_6") (pintype "input"))
      (node (ref "U11") (pin "A7") (pinfunction "DN1_A7") (pintype "input"))
      (node (ref "U11") (pin "B7") (pinfunction "DN2_B7") (pintype "input"))
    )
    (net (code "100") (name "VBAT") (class "Default")
      (node (ref "C10") (pin "2") (pinfunction "2_2") (pintype "input"))
      (node (ref "C11") (pin "2") (pinfunction "2_2") (pintype "input"))
      (node (ref "C12") (pin "1") (pinfunction "1_1") (pintype "input"))
      (node (ref "C21") (pin "2") (pinfunction "2_2") (pintype "input"))
      (node (ref "C22") (pin "2") (pinfunction "2_2") (pintype "input"))
      (node (ref "C23") (pin "2") (pinfunction "2_2") (pintype "input"))
      (node (ref "C9") (pin "2") (pinfunction "2_2") (pintype "input"))
      (node (ref "R1") (pin "2") (pinfunction "2_2") (pintype "input"))
      (node (ref "R45") (pin "1") (pinfunction "1_1") (pintype "input"))
      (node (ref "R6") (pin "2") (pinfunction "2_2") (pintype "input"))
      (node (ref "U2") (pin "1") (pinfunction "C_1") (pintype "input"))
      (node (ref "U4") (pin "2") (pinfunction "VIN_2") (pintype "input"))
      (node (ref "U6") (pin "2") (pinfunction "VIN_2") (pintype "input"))
    )
    (net (code "101") (name "unconnected-(H4-Pad3)") (class "Default")
      (node (ref "H4") (pin "3") (pinfunction "3_3") (pintype "input+no_connect"))
    )
    (net (code "102") (name "unconnected-(H4-Pad4)") (class "Default")
      (node (ref "H4") (pin "4") (pinfunction "4_4") (pintype "input+no_connect"))
    )
    (net (code "103") (name "unconnected-(H9-Pad5)") (class "Default")
      (node (ref "H9") (pin "5") (pinfunction "5_5") (pintype "input+no_connect"))
    )
    (net (code "104") (name "unconnected-(H9-Pad6)") (class "Default")
      (node (ref "H9") (pin "6") (pinfunction "6_6") (pintype "input+no_connect"))
    )
    (net (code "105") (name "unconnected-(H9-Pad8)") (class "Default")
      (node (ref "H9") (pin "8") (pinfunction "8_8") (pintype "input+no_connect"))
    )
    (net (code "106") (name "unconnected-(U9-CLK-Pad20)") (class "Default")
      (node (ref "U9") (pin "20") (pinfunction "CLK_20") (pintype "input+no_connect"))
    )
    (net (code "107") (name "unconnected-(U9-CMD-Pad19)") (class "Default")
      (node (ref "U9") (pin "19") (pinfunction "CMD_19") (pintype "input+no_connect"))
    )
    (net (code "108") (name "unconnected-(U9-IO2-Pad24)") (class "Default")
      (node (ref "U9") (pin "24") (pinfunction "IO2_24") (pintype "input+no_connect"))
    )
    (net (code "109") (name "unconnected-(U9-IO4-Pad26)") (class "Default")
      (node (ref "U9") (pin "26") (pinfunction "IO4_26") (pintype "input+no_connect"))
    )
    (net (code "110") (name "unconnected-(U9-IO16-Pad27)") (class "Default")
      (node (ref "U9") (pin "27") (pinfunction "IO16_27") (pintype "input+no_connect"))
    )
    (net (code "111") (name "unconnected-(U9-IO25-Pad10)") (class "Default")
      (node (ref "U9") (pin "10") (pinfunction "IO25_10") (pintype "input"))
    )
    (net (code "112") (name "unconnected-(U9-IO26-Pad11)") (class "Default")
      (node (ref "U9") (pin "11") (pinfunction "IO26_11") (pintype "input"))
    )
    (net (code "113") (name "unconnected-(U9-IO27-Pad12)") (class "Default")
      (node (ref "U9") (pin "12") (pinfunction "IO27_12") (pintype "input"))
    )
    (net (code "114") (name "unconnected-(U9-IO34-Pad6)") (class "Default")
      (node (ref "U9") (pin "6") (pinfunction "IO34_6") (pintype "input+no_connect"))
    )
    (net (code "115") (name "unconnected-(U9-IO35-Pad7)") (class "Default")
      (node (ref "U9") (pin "7") (pinfunction "IO35_7") (pintype "input+no_connect"))
    )
    (net (code "116") (name "unconnected-(U9-NC-Pad32)") (class "Default")
      (node (ref "U9") (pin "32") (pinfunction "NC_32") (pintype "input+no_connect"))
    )
    (net (code "117") (name "unconnected-(U9-SD2-Pad17)") (class "Default")
      (node (ref "U9") (pin "17") (pinfunction "SD2_17") (pintype "input+no_connect"))
    )
    (net (code "118") (name "unconnected-(U9-SD3-Pad18)") (class "Default")
      (node (ref "U9") (pin "18") (pinfunction "SD3_18") (pintype "input+no_connect"))
    )
    (net (code "119") (name "unconnected-(U9-SDI-Pad22)") (class "Default")
      (node (ref "U9") (pin "22") (pinfunction "SDI_22") (pintype "input+no_connect"))
    )
    (net (code "120") (name "unconnected-(U9-SDO-Pad21)") (class "Default")
      (node (ref "U9") (pin "21") (pinfunction "SDO_21") (pintype "input+no_connect"))
    )
    (net (code "121") (name "unconnected-(U9-SENSOR_VN-Pad5)") (class "Default")
      (node (ref "U9") (pin "5") (pinfunction "SENSOR_VN_5") (pintype "input+no_connect"))
    )
    (net (code "122") (name "unconnected-(U9-SENSOR_VP-Pad4)") (class "Default")
      (node (ref "U9") (pin "4") (pinfunction "SENSOR_VP_4") (pintype "input+no_connect"))
    )
    (net (code "123") (name "unconnected-(U10-CTS#-Pad9)") (class "Default")
      (node (ref "U10") (pin "9") (pinfunction "CTS#_9") (pintype "input+no_connect"))
    )
    (net (code "124") (name "unconnected-(U10-DCD#-Pad12)") (class "Default")
      (node (ref "U10") (pin "12") (pinfunction "DCD#_12") (pintype "input+no_connect"))
    )
    (net (code "125") (name "unconnected-(U10-DSR#-Pad10)") (class "Default")
      (node (ref "U10") (pin "10") (pinfunction "DSR#_10") (pintype "input+no_connect"))
    )
    (net (code "126") (name "unconnected-(U10-NC.-Pad7)") (class "Default")
      (node (ref "U10") (pin "7") (pinfunction "NC._7") (pintype "input+no_connect"))
    )
    (net (code "127") (name "unconnected-(U10-NC.-Pad8)") (class "Default")
      (node (ref "U10") (pin "8") (pinfunction "NC._8") (pintype "input+no_connect"))
    )
    (net (code "128") (name "unconnected-(U10-R232-Pad15)") (class "Default")
      (node (ref "U10") (pin "15") (pinfunction "R232_15") (pintype "input+no_connect"))
    )
    (net (code "129") (name "unconnected-(U10-RI#-Pad11)") (class "Default")
      (node (ref "U10") (pin "11") (pinfunction "RI#_11") (pintype "input+no_connect"))
    )
    (net (code "130") (name "unconnected-(U11-SBU1-PadA8)") (class "Default")
      (node (ref "U11") (pin "A8") (pinfunction "SBU1_A8") (pintype "input+no_connect"))
    )
    (net (code "131") (name "unconnected-(U11-SBU2-PadB8)") (class "Default")
      (node (ref "U11") (pin "B8") (pinfunction "SBU2_B8") (pintype "input+no_connect"))
    )
  )
)
